# DCTCXO.net
KiCad netlist of a schematic drawn in Altium Designer
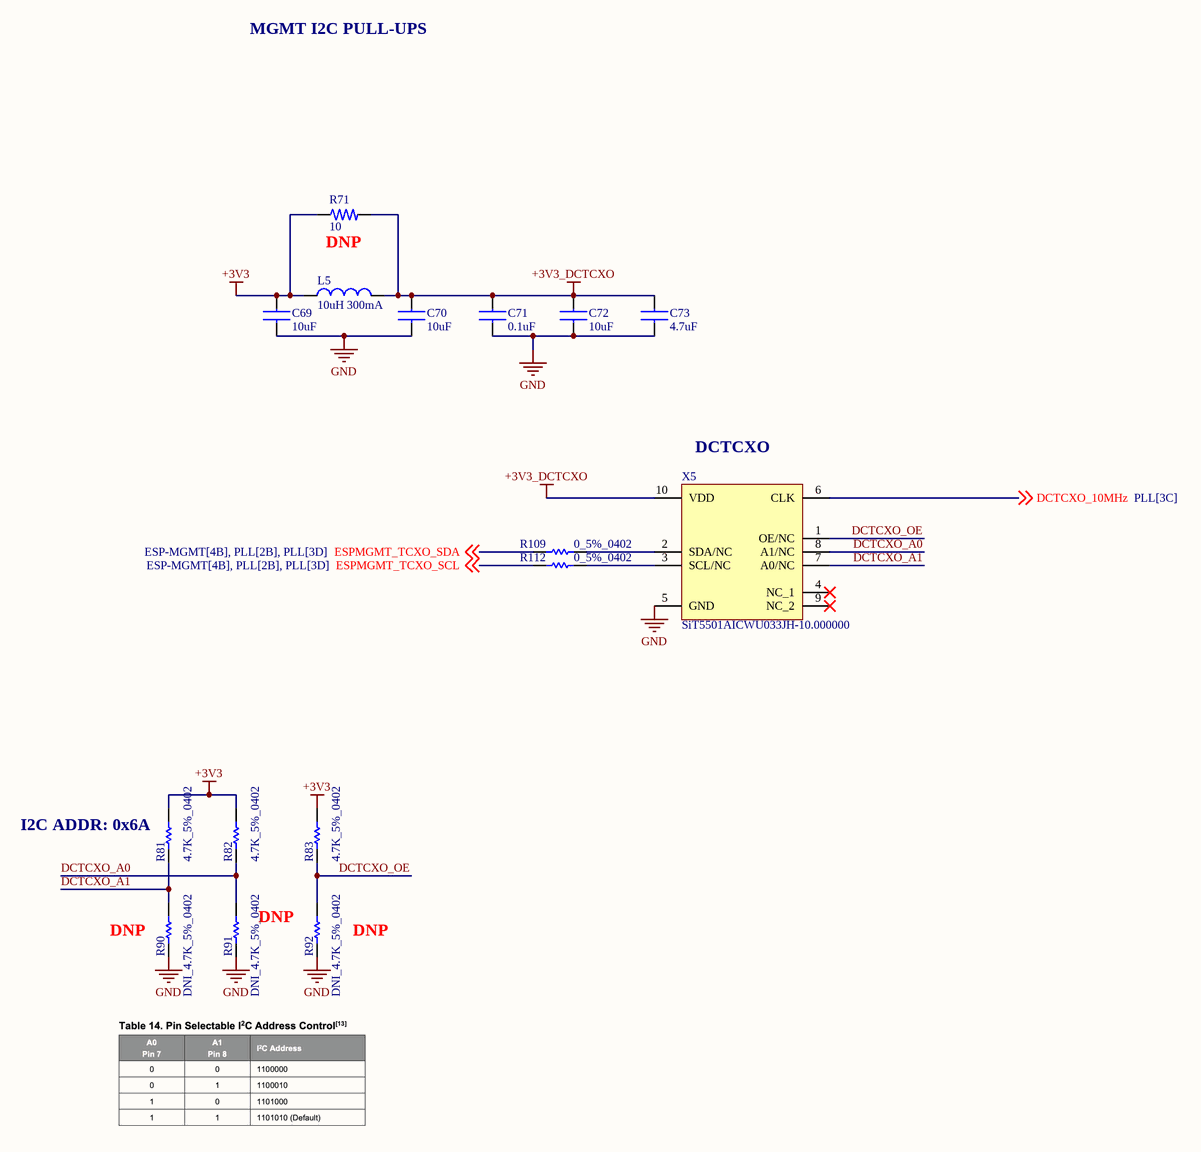
[diagram p0: DCTCXO.SchDoc]

(export (version "E")
  (design (tool "Eeschema 10.0.6"))
  (components
    (comp (ref "C69")
      (value "10uF")
      (footprint "CAP_0402")
      (description "Cap Ceramic 10uF 6.3V X5R 20% SMD 0402 85°C Paper T/R")
      (fields
        (field (name "MANUFACTURER") "Samsung")
        (field (name "MANUFACTURER PART NUMBER") "CL05A106MQ5NUNC")
      )
      (libsource (lib "LotusSound") (part "CAP_CL05A106MQ5NUNC"))
    )
    (comp (ref "C70")
      (value "10uF")
      (footprint "CAP_0402")
      (description "Cap Ceramic 10uF 6.3V X5R 20% SMD 0402 85°C Paper T/R")
      (fields
        (field (name "MANUFACTURER") "Samsung")
        (field (name "MANUFACTURER PART NUMBER") "CL05A106MQ5NUNC")
      )
      (libsource (lib "LotusSound") (part "CAP_CL05A106MQ5NUNC"))
    )
    (comp (ref "C71")
      (value "0.1uF")
      (footprint "CAP_0402")
      (description "Cap Ceramic 0.1uF 16V X7R 10% SMD 0402 125C Paper T/R")
      (fields
        (field (name "MANUFACTURER") "Murata")
        (field (name "MANUFACTURER PART NUMBER") "GCM155R71C104KA55J")
      )
      (libsource (lib "LotusSound") (part "CAP_GCM155R71C104KA55J"))
    )
    (comp (ref "C72")
      (value "10uF")
      (footprint "CAP_0402")
      (description "Cap Ceramic 10uF 6.3V X5R 20% SMD 0402 85°C Paper T/R")
      (fields
        (field (name "MANUFACTURER") "Samsung")
        (field (name "MANUFACTURER PART NUMBER") "CL05A106MQ5NUNC")
      )
      (libsource (lib "LotusSound") (part "CAP_CL05A106MQ5NUNC"))
    )
    (comp (ref "C73")
      (value "4.7uF")
      (footprint "CAP_0402")
      (description "Multilayer Ceramic Capacitors MLCC - SMD/SMT 4.7uF 10V X5R +/-20% 0402 Gen Purp")
      (fields
        (field (name "MANUFACTURER") "Taiyo Yuden")
        (field (name "MANUFACTURER PART NUMBER") "LMK105BBJ475MVLF")
      )
      (libsource (lib "LotusSound") (part "CAP_LMK105BBJ475MVLF"))
    )
    (comp (ref "L5")
      (value "10uH 300mA")
      (footprint "L_490-LQM18DN100M70LCT-ND")
      (description "Inductor, 10Uh, 0.3A, Multilayer Rohs Compliant: Yes")
      (fields
        (field (name "MANUFACTURER") "Murata")
        (field (name "MANUFACTURER PART NUMBER") "LQM18DN100M70L")
      )
      (libsource (lib "LotusSound") (part "L_LQM18DN100M70L"))
    )
    (comp (ref "R71")
      (value "10")
      (footprint "RES_0402")
      (description "Res General Purpose Thick Film 0402 10 Ohm 1% 1/16W ±200ppm/°C Molded SMD Paper T/R")
      (fields
        (field (name "MANUFACTURER") "Yageo")
        (field (name "MANUFACTURER PART NUMBER") "RC0402FR-0710RL")
      )
      (libsource (lib "LotusSound") (part "RES_RC0402FR-0710RL"))
    )
    (comp (ref "R81")
      (value "4.7K_5%_0402")
      (footprint "RESC1005X40X25LL05T05")
      (fields (field (name "PART NUMBER") "CRCW04024K70JNTD") (field (name "MANUFACTURER") "Vishay Dale"))
      (libsource (lib "Altium Content Vault") (part "RES"))
    )
    (comp (ref "R82")
      (value "4.7K_5%_0402")
      (footprint "RESC1005X40X25LL05T05")
      (fields (field (name "PART NUMBER") "CRCW04024K70JNTD") (field (name "MANUFACTURER") "Vishay Dale"))
      (libsource (lib "Altium Content Vault") (part "RES"))
    )
    (comp (ref "R83")
      (value "4.7K_5%_0402")
      (footprint "RESC1005X40X25LL05T05")
      (fields (field (name "PART NUMBER") "CRCW04024K70JNTD") (field (name "MANUFACTURER") "Vishay Dale"))
      (libsource (lib "Altium Content Vault") (part "RES"))
    )
    (comp (ref "R90")
      (value "DNI_4.7K_5%_0402")
      (footprint "RESC1005X40X25LL05T05")
      (fields (field (name "PART NUMBER") "CRCW04024K70JNTD") (field (name "MANUFACTURER") "Vishay Dale"))
      (libsource (lib "Altium Content Vault") (part "RES"))
    )
    (comp (ref "R91")
      (value "DNI_4.7K_5%_0402")
      (footprint "RESC1005X40X25LL05T05")
      (fields (field (name "PART NUMBER") "CRCW04024K70JNTD") (field (name "MANUFACTURER") "Vishay Dale"))
      (libsource (lib "Altium Content Vault") (part "RES"))
    )
    (comp (ref "R92")
      (value "DNI_4.7K_5%_0402")
      (footprint "RESC1005X40X25LL05T05")
      (fields (field (name "PART NUMBER") "CRCW04024K70JNTD") (field (name "MANUFACTURER") "Vishay Dale"))
      (libsource (lib "Altium Content Vault") (part "RES"))
    )
    (comp (ref "R109")
      (value "0_5%_0402")
      (footprint "RESC1005X40X25ML05T10")
      (fields (field (name "MANUFACTURER") "Panasonic") (field (name "PART NUMBER") "ERJ-U020R00X"))
      (libsource (lib "Altium Content Vault") (part "RES"))
    )
    (comp (ref "R112")
      (value "0_5%_0402")
      (footprint "RESC1005X40X25ML05T10")
      (fields (field (name "MANUFACTURER") "Panasonic") (field (name "PART NUMBER") "ERJ-U020R00X"))
      (libsource (lib "Altium Content Vault") (part "RES"))
    )
    (comp (ref "X5")
      (value "SiT5501AICWU033JH-10.000000")
      (footprint "XTAL_SiT5501_70x50")
      (description "1 MHz  60 MHz, Elite X Stratum 3E Precision Oscillator")
      (fields (field (name "MANUFACTURER_PART_NUMBER") "SiT5501AI-WU033JH-10.000000"))
      (libsource (lib "LotusSound") (part "XTAL_SIT5501AI-WUG33JT-10.000000"))
    )
  )
  (nets
    (net (code "1") (name "+3V3") (class "Default")
      (node (ref "C69") (pin "2") (pinfunction "2_2") (pintype "passive"))
      (node (ref "L5") (pin "1") (pinfunction "1_1") (pintype "passive"))
      (node (ref "R71") (pin "1") (pinfunction "1_1") (pintype "passive"))
      (node (ref "R81") (pin "2") (pinfunction "2_2") (pintype "passive"))
      (node (ref "R82") (pin "2") (pinfunction "2_2") (pintype "passive"))
      (node (ref "R83") (pin "2") (pinfunction "2_2") (pintype "passive"))
    )
    (net (code "2") (name "+3V3_DCTCXO") (class "Default")
      (node (ref "C70") (pin "2") (pinfunction "2_2") (pintype "passive"))
      (node (ref "C71") (pin "2") (pinfunction "2_2") (pintype "passive"))
      (node (ref "C72") (pin "2") (pinfunction "2_2") (pintype "passive"))
      (node (ref "C73") (pin "2") (pinfunction "2_2") (pintype "passive"))
      (node (ref "L5") (pin "2") (pinfunction "2_2") (pintype "passive"))
      (node (ref "R71") (pin "2") (pinfunction "2_2") (pintype "passive"))
      (node (ref "X5") (pin "10") (pinfunction "VDD_10") (pintype "passive"))
    )
    (net (code "3") (name "/DCTCXO_A0") (class "Default")
      (node (ref "R82") (pin "1") (pinfunction "1_1") (pintype "passive"))
      (node (ref "R91") (pin "2") (pinfunction "2_2") (pintype "passive"))
      (node (ref "X5") (pin "8") (pinfunction "A1/NC_8") (pintype "passive"))
    )
    (net (code "4") (name "/DCTCXO_A1") (class "Default")
      (node (ref "R81") (pin "1") (pinfunction "1_1") (pintype "passive"))
      (node (ref "R90") (pin "2") (pinfunction "2_2") (pintype "passive"))
      (node (ref "X5") (pin "7") (pinfunction "A0/NC_7") (pintype "passive"))
    )
    (net (code "5") (name "/DCTCXO_OE") (class "Default")
      (node (ref "R83") (pin "1") (pinfunction "1_1") (pintype "passive"))
      (node (ref "R92") (pin "2") (pinfunction "2_2") (pintype "passive"))
      (node (ref "X5") (pin "1") (pinfunction "OE/NC_1") (pintype "passive"))
    )
    (net (code "6") (name "DCTCXO_10MHz") (class "Default")
      (node (ref "X5") (pin "6") (pinfunction "CLK_6") (pintype "passive"))
    )
    (net (code "7") (name "ESPMGMT_TCXO_SCL") (class "Default")
      (node (ref "R112") (pin "1") (pinfunction "1_1") (pintype "passive"))
    )
    (net (code "8") (name "ESPMGMT_TCXO_SDA") (class "Default")
      (node (ref "R109") (pin "1") (pinfunction "1_1") (pintype "passive"))
    )
    (net (code "9") (name "GND") (class "Default")
      (node (ref "C69") (pin "1") (pinfunction "1_1") (pintype "passive"))
      (node (ref "C70") (pin "1") (pinfunction "1_1") (pintype "passive"))
      (node (ref "C71") (pin "1") (pinfunction "1_1") (pintype "passive"))
      (node (ref "C72") (pin "1") (pinfunction "1_1") (pintype "passive"))
      (node (ref "C73") (pin "1") (pinfunction "1_1") (pintype "passive"))
      (node (ref "R90") (pin "1") (pinfunction "1_1") (pintype "passive"))
      (node (ref "R91") (pin "1") (pinfunction "1_1") (pintype "passive"))
      (node (ref "R92") (pin "1") (pinfunction "1_1") (pintype "passive"))
      (node (ref "X5") (pin "5") (pinfunction "GND_5") (pintype "passive"))
    )
    (net (code "10") (name "Net-(X5-SCL{slash}NC)") (class "Default")
      (node (ref "R112") (pin "2") (pinfunction "2_2") (pintype "passive"))
      (node (ref "X5") (pin "3") (pinfunction "SCL/NC_3") (pintype "passive"))
    )
    (net (code "11") (name "Net-(X5-SDA{slash}NC)") (class "Default")
      (node (ref "R109") (pin "2") (pinfunction "2_2") (pintype "passive"))
      (node (ref "X5") (pin "2") (pinfunction "SDA/NC_2") (pintype "passive"))
    )
    (net (code "12") (name "unconnected-(X5-NC_1-Pad4)") (class "Default")
      (node (ref "X5") (pin "4") (pinfunction "NC_1_4") (pintype "passive+no_connect"))
    )
    (net (code "13") (name "unconnected-(X5-NC_2-Pad9)") (class "Default")
      (node (ref "X5") (pin "9") (pinfunction "NC_2_9") (pintype "passive+no_connect"))
    )
  )
)
